# launchpad.net
KiCad netlist of a schematic drawn in EAGLE
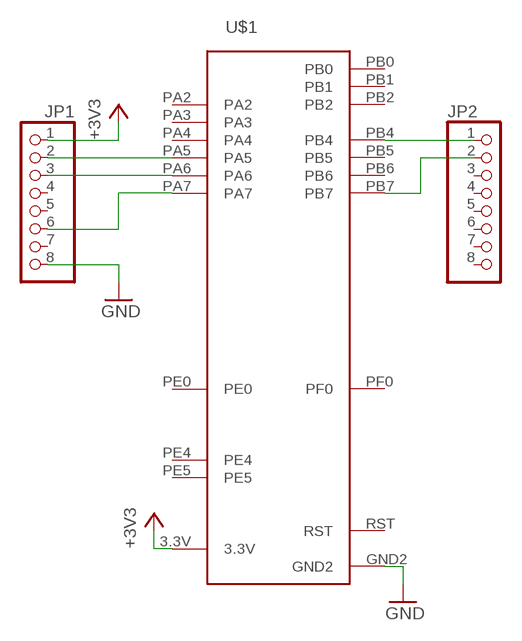
[diagram p0: schematic, sheet 1]

(export (version "E")
  (design (tool "Eeschema 10.0.6"))
  (components
    (comp (ref "JP1")
      (value "PINHD-1X8")
      (footprint "eagle-import:1X08")
      (libsource (lib "eagle-import") (part "PINHD-1X8"))
    )
    (comp (ref "JP2")
      (value "PINHD-1X8")
      (footprint "eagle-import:1X08")
      (libsource (lib "eagle-import") (part "PINHD-1X8"))
    )
    (comp (ref "U$1")
      (value "STELLARIS-LAUNCHPAD-COMPATIBLESTELLARIS-LAUNCHPAD-COMPATIBLE")
      (footprint "eagle-import:LAUNCHPAD-COMPATIBLE")
      (libsource (lib "eagle-import") (part "STELLARIS-LAUNCHPAD-COMPATIBLESTELLARIS-LAUNCHPAD-COMPATIBLE"))
    )
  )
  (nets
    (net (code "1") (name "+3V3") (class "Default")
      (node (ref "JP1") (pin "1") (pinfunction "1_1") (pintype "passive"))
      (node (ref "U$1") (pin "3.3V") (pinfunction "3.3V_3.3V") (pintype "power_in"))
    )
    (net (code "2") (name "/RST") (class "Default")
      (node (ref "U$1") (pin "RST") (pinfunction "RST_RST") (pintype "power_in"))
    )
    (net (code "3") (name "GND") (class "Default")
      (node (ref "JP1") (pin "8") (pinfunction "8_8") (pintype "passive"))
      (node (ref "U$1") (pin "GND2") (pinfunction "GND2_GND2") (pintype "power_in"))
    )
    (net (code "4") (name "Net-(JP1-Pad2)") (class "Default")
      (node (ref "JP1") (pin "2") (pinfunction "2_2") (pintype "passive"))
      (node (ref "U$1") (pin "PA5") (pinfunction "PA5_PA5") (pintype "bidirectional"))
    )
    (net (code "5") (name "Net-(JP1-Pad3)") (class "Default")
      (node (ref "JP1") (pin "3") (pinfunction "3_3") (pintype "passive"))
      (node (ref "U$1") (pin "PA6") (pinfunction "PA6_PA6") (pintype "bidirectional"))
    )
    (net (code "6") (name "Net-(JP1-Pad6)") (class "Default")
      (node (ref "JP1") (pin "6") (pinfunction "6_6") (pintype "passive"))
      (node (ref "U$1") (pin "PA7") (pinfunction "PA7_PA7") (pintype "bidirectional"))
    )
    (net (code "7") (name "Net-(JP2-Pad1)") (class "Default")
      (node (ref "JP2") (pin "1") (pinfunction "1_1") (pintype "passive"))
      (node (ref "U$1") (pin "PB4") (pinfunction "PB4_PB4") (pintype "bidirectional"))
    )
    (net (code "8") (name "Net-(JP2-Pad2)") (class "Default")
      (node (ref "JP2") (pin "2") (pinfunction "2_2") (pintype "passive"))
      (node (ref "U$1") (pin "PB7") (pinfunction "PB7_PB7") (pintype "bidirectional"))
    )
    (net (code "9") (name "unconnected-(JP1-Pad4)") (class "Default")
      (node (ref "JP1") (pin "4") (pinfunction "4_4") (pintype "passive"))
    )
    (net (code "10") (name "unconnected-(JP1-Pad5)") (class "Default")
      (node (ref "JP1") (pin "5") (pinfunction "5_5") (pintype "passive"))
    )
    (net (code "11") (name "unconnected-(JP1-Pad7)") (class "Default")
      (node (ref "JP1") (pin "7") (pinfunction "7_7") (pintype "passive"))
    )
    (net (code "12") (name "unconnected-(JP2-Pad3)") (class "Default")
      (node (ref "JP2") (pin "3") (pinfunction "3_3") (pintype "passive"))
    )
    (net (code "13") (name "unconnected-(JP2-Pad4)") (class "Default")
      (node (ref "JP2") (pin "4") (pinfunction "4_4") (pintype "passive"))
    )
    (net (code "14") (name "unconnected-(JP2-Pad5)") (class "Default")
      (node (ref "JP2") (pin "5") (pinfunction "5_5") (pintype "passive"))
    )
    (net (code "15") (name "unconnected-(JP2-Pad6)") (class "Default")
      (node (ref "JP2") (pin "6") (pinfunction "6_6") (pintype "passive"))
    )
    (net (code "16") (name "unconnected-(JP2-Pad7)") (class "Default")
      (node (ref "JP2") (pin "7") (pinfunction "7_7") (pintype "passive"))
    )
    (net (code "17") (name "unconnected-(JP2-Pad8)") (class "Default")
      (node (ref "JP2") (pin "8") (pinfunction "8_8") (pintype "passive"))
    )
    (net (code "18") (name "unconnected-(U$1-PadPA2)") (class "Default")
      (node (ref "U$1") (pin "PA2") (pinfunction "PA2_PA2") (pintype "bidirectional"))
    )
    (net (code "19") (name "unconnected-(U$1-PadPA3)") (class "Default")
      (node (ref "U$1") (pin "PA3") (pinfunction "PA3_PA3") (pintype "bidirectional"))
    )
    (net (code "20") (name "unconnected-(U$1-PadPA4)") (class "Default")
      (node (ref "U$1") (pin "PA4") (pinfunction "PA4_PA4") (pintype "bidirectional"))
    )
    (net (code "21") (name "unconnected-(U$1-PadPB0)") (class "Default")
      (node (ref "U$1") (pin "PB0") (pinfunction "PB0_PB0") (pintype "bidirectional"))
    )
    (net (code "22") (name "unconnected-(U$1-PadPB1)") (class "Default")
      (node (ref "U$1") (pin "PB1") (pinfunction "PB1_PB1") (pintype "bidirectional"))
    )
    (net (code "23") (name "unconnected-(U$1-PadPB2)") (class "Default")
      (node (ref "U$1") (pin "PB2") (pinfunction "PB2_PB2") (pintype "bidirectional"))
    )
    (net (code "24") (name "unconnected-(U$1-PadPB5)") (class "Default")
      (node (ref "U$1") (pin "PB5") (pinfunction "PB5_PB5") (pintype "bidirectional"))
    )
    (net (code "25") (name "unconnected-(U$1-PadPB6)") (class "Default")
      (node (ref "U$1") (pin "PB6") (pinfunction "PB6_PB6") (pintype "bidirectional"))
    )
    (net (code "26") (name "unconnected-(U$1-PadPE0)") (class "Default")
      (node (ref "U$1") (pin "PE0") (pinfunction "PE0_PE0") (pintype "bidirectional"))
    )
    (net (code "27") (name "unconnected-(U$1-PadPE4)") (class "Default")
      (node (ref "U$1") (pin "PE4") (pinfunction "PE4_PE4") (pintype "bidirectional"))
    )
    (net (code "28") (name "unconnected-(U$1-PadPE5)") (class "Default")
      (node (ref "U$1") (pin "PE5") (pinfunction "PE5_PE5") (pintype "bidirectional"))
    )
    (net (code "29") (name "unconnected-(U$1-PadPF0)") (class "Default")
      (node (ref "U$1") (pin "PF0") (pinfunction "PF0_PF0") (pintype "bidirectional"))
    )
  )
)
